# MOUNTING.net
KiCad netlist of a schematic drawn in Altium Designer
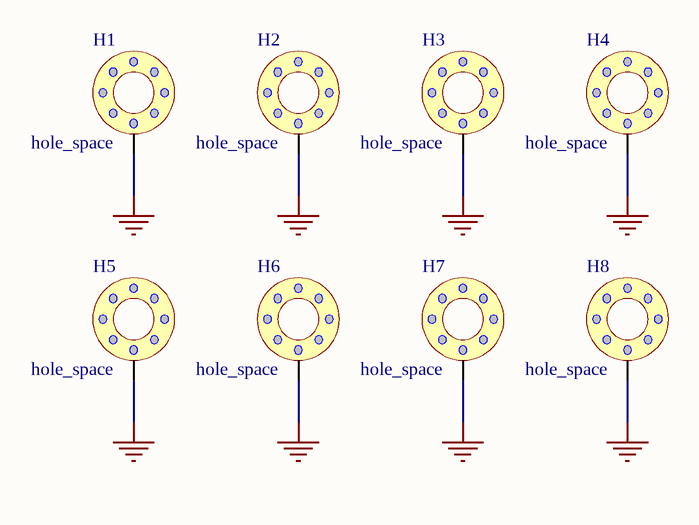
[diagram p0: MOUNTING.SchDoc]

(export (version "E")
  (design (tool "Eeschema 10.0.6"))
  (components
    (comp (ref "H1")
      (value "hole_space")
      (footprint "HEX-M3_NoVia_Smaller")
      (libsource (lib "IFBschelib") (part "hole_space"))
    )
    (comp (ref "H2")
      (value "hole_space")
      (footprint "HEX-M3_NoVia_Smaller")
      (libsource (lib "IFBschelib") (part "hole_space"))
    )
    (comp (ref "H3")
      (value "hole_space")
      (footprint "HEX-M3_NoVia_Smaller")
      (libsource (lib "IFBschelib") (part "hole_space"))
    )
    (comp (ref "H4")
      (value "hole_space")
      (footprint "HEX-M3_NoVia_Smaller")
      (libsource (lib "IFBschelib") (part "hole_space"))
    )
    (comp (ref "H5")
      (value "hole_space")
      (footprint "HEX-M3_NoVia_Smaller")
      (libsource (lib "IFBschelib") (part "hole_space"))
    )
    (comp (ref "H6")
      (value "hole_space")
      (footprint "HEX-M3_NoVia_Smaller")
      (libsource (lib "IFBschelib") (part "hole_space"))
    )
    (comp (ref "H7")
      (value "hole_space")
      (footprint "HEX-M3_NoVia_Smaller")
      (libsource (lib "IFBschelib") (part "hole_space"))
    )
    (comp (ref "H8")
      (value "hole_space")
      (footprint "HEX-M3_NoVia_Smaller")
      (libsource (lib "IFBschelib") (part "hole_space"))
    )
  )
  (nets
    (net (code "1") (name "GND") (class "Default")
      (node (ref "H1") (pin "1") (pinfunction "1_1") (pintype "passive"))
      (node (ref "H2") (pin "1") (pinfunction "1_1") (pintype "passive"))
      (node (ref "H3") (pin "1") (pinfunction "1_1") (pintype "passive"))
      (node (ref "H4") (pin "1") (pinfunction "1_1") (pintype "passive"))
      (node (ref "H5") (pin "1") (pinfunction "1_1") (pintype "passive"))
      (node (ref "H6") (pin "1") (pinfunction "1_1") (pintype "passive"))
      (node (ref "H7") (pin "1") (pinfunction "1_1") (pintype "passive"))
      (node (ref "H8") (pin "1") (pinfunction "1_1") (pintype "passive"))
    )
  )
)
